# MainBoard_V2.net
KiCad netlist of a schematic drawn in Altium Designer
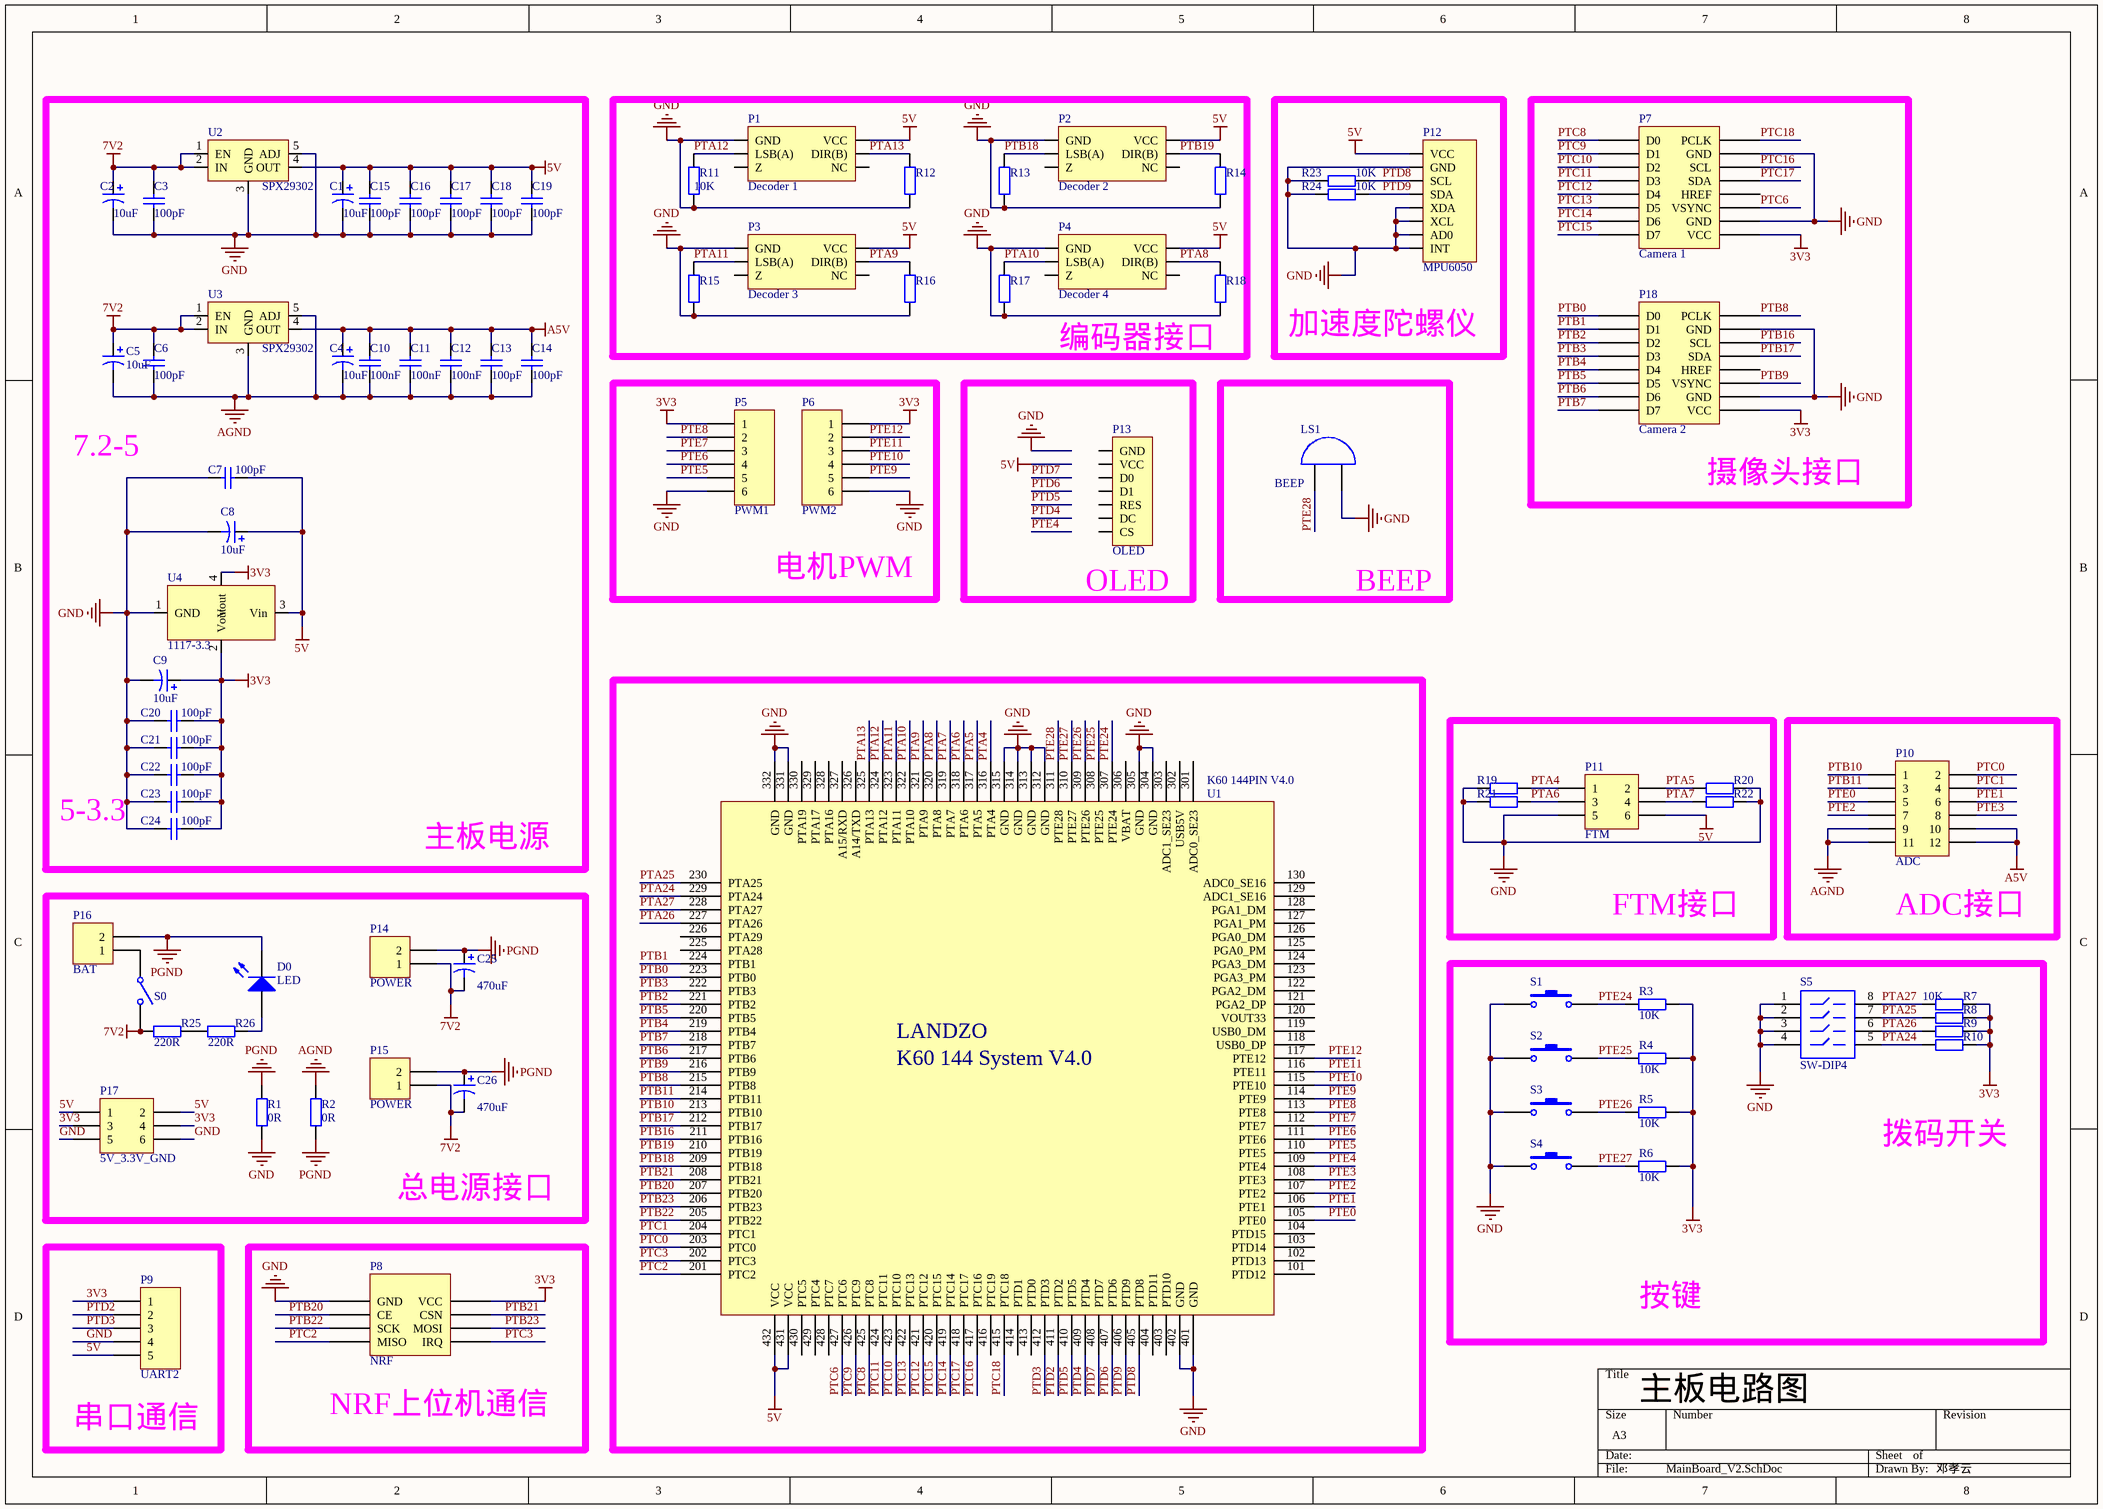
[diagram p0: MainBoard_V2.SchDoc]

(export (version "E")
  (design (tool "Eeschema 10.0.6"))
  (components
    (comp (ref "C1")
      (value "10uF")
      (footprint "1206 C tan")
      (description "Polarized Capacitor (Radial)")
      (fields (field (name "Comment") "Cap Pol1"))
      (libsource (lib "Miscellaneous Devices") (part "Cap Pol1"))
    )
    (comp (ref "C2")
      (value "10uF")
      (footprint "1206 C tan")
      (description "Polarized Capacitor (Radial)")
      (fields (field (name "Comment") "Cap Pol1"))
      (libsource (lib "Miscellaneous Devices") (part "Cap Pol1"))
    )
    (comp (ref "C3")
      (value "100pF")
      (footprint "1206 C")
      (description "Capacitor (Semiconductor SIM Model)")
      (fields (field (name "Comment") "Cap Semi"))
      (libsource (lib "Miscellaneous Devices") (part "Cap Semi"))
    )
    (comp (ref "C4")
      (value "10uF")
      (footprint "1206 C tan")
      (description "Polarized Capacitor (Radial)")
      (fields (field (name "Comment") "Cap Pol1"))
      (libsource (lib "Miscellaneous Devices") (part "Cap Pol1"))
    )
    (comp (ref "C5")
      (value "10uF")
      (footprint "1206 C tan")
      (description "Polarized Capacitor (Radial)")
      (fields (field (name "Comment") "Cap Pol1"))
      (libsource (lib "Miscellaneous Devices") (part "Cap Pol1"))
    )
    (comp (ref "C6")
      (value "100pF")
      (footprint "1206 C")
      (description "Capacitor (Semiconductor SIM Model)")
      (fields (field (name "Comment") "Cap Semi"))
      (libsource (lib "Miscellaneous Devices") (part "Cap Semi"))
    )
    (comp (ref "C7")
      (value "100pF")
      (footprint "1206 C")
      (description "Capacitor (Semiconductor SIM Model)")
      (fields (field (name "Comment") "Cap Semi"))
      (libsource (lib "Miscellaneous Devices") (part "Cap Semi"))
    )
    (comp (ref "C8")
      (value "10uF")
      (footprint "1206 C tan")
      (description "Polarized Capacitor (Radial)")
      (fields (field (name "Comment") "Cap Pol1"))
      (libsource (lib "Miscellaneous Devices") (part "Cap Pol1"))
    )
    (comp (ref "C9")
      (value "10uF")
      (footprint "1206 C tan")
      (description "Polarized Capacitor (Radial)")
      (fields (field (name "Comment") "Cap Pol1"))
      (libsource (lib "Miscellaneous Devices") (part "Cap Pol1"))
    )
    (comp (ref "C10")
      (value "100nF")
      (footprint "0805 C")
      (description "Capacitor")
      (fields (field (name "Comment") "Cap"))
      (libsource (lib "Miscellaneous Devices") (part "Cap"))
    )
    (comp (ref "C11")
      (value "100nF")
      (footprint "0805 C")
      (description "Capacitor")
      (fields (field (name "Comment") "Cap"))
      (libsource (lib "Miscellaneous Devices") (part "Cap"))
    )
    (comp (ref "C12")
      (value "100nF")
      (footprint "0805 C")
      (description "Capacitor")
      (fields (field (name "Comment") "Cap"))
      (libsource (lib "Miscellaneous Devices") (part "Cap"))
    )
    (comp (ref "C13")
      (value "100pF")
      (footprint "0805 C")
      (description "Capacitor")
      (fields (field (name "Comment") "Cap"))
      (libsource (lib "Miscellaneous Devices") (part "Cap"))
    )
    (comp (ref "C14")
      (value "100pF")
      (footprint "0805 C")
      (description "Capacitor")
      (fields (field (name "Comment") "Cap"))
      (libsource (lib "Miscellaneous Devices") (part "Cap"))
    )
    (comp (ref "C15")
      (value "100pF")
      (footprint "0805 C")
      (description "Capacitor")
      (fields (field (name "Comment") "Cap"))
      (libsource (lib "Miscellaneous Devices") (part "Cap"))
    )
    (comp (ref "C16")
      (value "100pF")
      (footprint "0805 C")
      (description "Capacitor")
      (fields (field (name "Comment") "Cap"))
      (libsource (lib "Miscellaneous Devices") (part "Cap"))
    )
    (comp (ref "C17")
      (value "100pF")
      (footprint "0805 C")
      (description "Capacitor")
      (fields (field (name "Comment") "Cap"))
      (libsource (lib "Miscellaneous Devices") (part "Cap"))
    )
    (comp (ref "C18")
      (value "100pF")
      (footprint "0805 C")
      (description "Capacitor")
      (fields (field (name "Comment") "Cap"))
      (libsource (lib "Miscellaneous Devices") (part "Cap"))
    )
    (comp (ref "C19")
      (value "100pF")
      (footprint "0805 C")
      (description "Capacitor")
      (fields (field (name "Comment") "Cap"))
      (libsource (lib "Miscellaneous Devices") (part "Cap"))
    )
    (comp (ref "C20")
      (value "100pF")
      (footprint "0805 C")
      (description "Capacitor")
      (fields (field (name "Comment") "Cap"))
      (libsource (lib "Miscellaneous Devices") (part "Cap"))
    )
    (comp (ref "C21")
      (value "100pF")
      (footprint "0805 C")
      (description "Capacitor")
      (fields (field (name "Comment") "Cap"))
      (libsource (lib "Miscellaneous Devices") (part "Cap"))
    )
    (comp (ref "C22")
      (value "100pF")
      (footprint "0805 C")
      (description "Capacitor")
      (fields (field (name "Comment") "Cap"))
      (libsource (lib "Miscellaneous Devices") (part "Cap"))
    )
    (comp (ref "C23")
      (value "100pF")
      (footprint "0805 C")
      (description "Capacitor")
      (fields (field (name "Comment") "Cap"))
      (libsource (lib "Miscellaneous Devices") (part "Cap"))
    )
    (comp (ref "C24")
      (value "100pF")
      (footprint "0805 C")
      (description "Capacitor")
      (fields (field (name "Comment") "Cap"))
      (libsource (lib "Miscellaneous Devices") (part "Cap"))
    )
    (comp (ref "C25")
      (value "470uF")
      (footprint "C pol")
      (description "Polarized Capacitor (Radial)")
      (fields (field (name "Comment") "Cap Pol1"))
      (libsource (lib "Miscellaneous Devices") (part "Cap Pol1"))
    )
    (comp (ref "C26")
      (value "470uF")
      (footprint "C pol")
      (description "Polarized Capacitor (Radial)")
      (fields (field (name "Comment") "Cap Pol1"))
      (libsource (lib "Miscellaneous Devices") (part "Cap Pol1"))
    )
    (comp (ref "D0")
      (value "LED")
      (footprint "0805 D")
      (description "Typical INFRARED GaAs LED")
      (libsource (lib "Miscellaneous Devices") (part "LED0"))
    )
    (comp (ref "K60 144PIN V4.0")
      (value "U1")
      (footprint "K60 V4.0")
      (description "Vcc5V。网标x代表排针。USB5V供外接USB使用的，不推荐使用。VBAT是给另一个晶振使用的，使用3.3V，可以不接。")
      (libsource (lib "最小系统板K60P144-V4.0") (part "K60 144PIN V4.0系统板"))
    )
    (comp (ref "LS1")
      (value "BEEP")
      (footprint "BEEP")
      (description "Electrical Bell")
      (libsource (lib "Miscellaneous Devices") (part "Bell"))
    )
    (comp (ref "P1")
      (value "Decoder 1")
      (footprint "BigHeader P3*2")
      (description "Header-6")
      (libsource (lib "Sch库") (part "Decoder"))
    )
    (comp (ref "P2")
      (value "Decoder 2")
      (footprint "BigHeader P3*2")
      (description "Header-6")
      (libsource (lib "Sch库") (part "Decoder"))
    )
    (comp (ref "P3")
      (value "Decoder 3")
      (footprint "BigHeader P3*2")
      (description "Header-6")
      (libsource (lib "Sch库") (part "Decoder"))
    )
    (comp (ref "P4")
      (value "Decoder 4")
      (footprint "BigHeader P3*2")
      (description "Header-6")
      (libsource (lib "Sch库") (part "Decoder"))
    )
    (comp (ref "P5")
      (value "PWM1")
      (footprint "Header P6")
      (description "Header, 6-Pin")
      (libsource (lib "") (part "Header 6_1"))
    )
    (comp (ref "P6")
      (value "PWM2")
      (footprint "Header P6")
      (description "Header, 6-Pin")
      (libsource (lib "Miscellaneous Connectors") (part "Header 6"))
    )
    (comp (ref "P7")
      (value "Camera 1")
      (footprint "FHeader P8*2")
      (description "3.3V")
      (libsource (lib "C车外接器件") (part "OV7725"))
    )
    (comp (ref "P8") (value "NRF") (footprint "NRF") (libsource (lib "C车外接器件") (part "NRF")))
    (comp (ref "P9")
      (value "UART2")
      (footprint "Header P5")
      (description "Header, 5-Pin")
      (libsource (lib "Miscellaneous Connectors") (part "Header 5"))
    )
    (comp (ref "P10")
      (value "ADC")
      (footprint "Header P6*2")
      (description "Header, 6-Pin, Dual row")
      (libsource (lib "Miscellaneous Connectors") (part "Header 6X2"))
    )
    (comp (ref "P11")
      (value "FTM")
      (footprint "Header P3*2")
      (description "Header, 3-Pin, Dual row")
      (libsource (lib "Miscellaneous Connectors") (part "Header 3X2"))
    )
    (comp (ref "P12")
      (value "MPU6050")
      (footprint "MPU6050")
      (description "Header-8")
      (libsource (lib "Sch库") (part "MPU6050"))
    )
    (comp (ref "P13")
      (value "OLED")
      (footprint "OLED P7")
      (description "Header-7")
      (libsource (lib "Sch库") (part "OLED"))
    )
    (comp (ref "P14")
      (value "POWER")
      (footprint "Connect 050-2")
      (description "Header, 2-Pin")
      (libsource (lib "Miscellaneous Connectors") (part "Header 2"))
    )
    (comp (ref "P15")
      (value "POWER")
      (footprint "Connect 050-2")
      (description "Header, 2-Pin")
      (libsource (lib "Miscellaneous Connectors") (part "Header 2"))
    )
    (comp (ref "P16")
      (value "BAT")
      (footprint "Connect 050-2")
      (description "Header, 2-Pin")
      (libsource (lib "Miscellaneous Connectors") (part "Header 2"))
    )
    (comp (ref "P17")
      (value "5V_3.3V_GND")
      (footprint "Header P3*2")
      (description "Header, 3-Pin, Dual row")
      (libsource (lib "Miscellaneous Connectors") (part "Header 3X2"))
    )
    (comp (ref "P18")
      (value "Camera 2")
      (footprint "FHeader P8*2")
      (description "3.3V")
      (libsource (lib "C车外接器件") (part "OV7725"))
    )
    (comp (ref "R1")
      (value "0R")
      (footprint "1206 R")
      (description "Resistor")
      (fields (field (name "Comment") "Res2"))
      (libsource (lib "Miscellaneous Devices") (part "Res2"))
    )
    (comp (ref "R2")
      (value "0R")
      (footprint "1206 R")
      (description "Resistor")
      (fields (field (name "Comment") "Res2"))
      (libsource (lib "Miscellaneous Devices") (part "Res2"))
    )
    (comp (ref "R3")
      (value "10K")
      (footprint "0805 R")
      (description "Resistor")
      (fields (field (name "Comment") "Res2"))
      (libsource (lib "") (part "Res2_1"))
    )
    (comp (ref "R4")
      (value "10K")
      (footprint "0805 R")
      (description "Resistor")
      (fields (field (name "Comment") "Res2"))
      (libsource (lib "") (part "Res2_1"))
    )
    (comp (ref "R5")
      (value "10K")
      (footprint "0805 R")
      (description "Resistor")
      (fields (field (name "Comment") "Res2"))
      (libsource (lib "") (part "Res2_1"))
    )
    (comp (ref "R6")
      (value "10K")
      (footprint "0805 R")
      (description "Resistor")
      (fields (field (name "Comment") "Res2"))
      (libsource (lib "") (part "Res2_1"))
    )
    (comp (ref "R7")
      (value "10K")
      (footprint "0805 R")
      (description "Resistor")
      (fields (field (name "Comment") "Res2"))
      (libsource (lib "") (part "Res2_1"))
    )
    (comp (ref "R8")
      (value "Res2")
      (footprint "0805 R")
      (description "Resistor")
      (libsource (lib "") (part "Res2_1"))
    )
    (comp (ref "R9")
      (value "Res2")
      (footprint "0805 R")
      (description "Resistor")
      (libsource (lib "") (part "Res2_1"))
    )
    (comp (ref "R10")
      (value "Res2")
      (footprint "0805 R")
      (description "Resistor")
      (libsource (lib "") (part "Res2_1"))
    )
    (comp (ref "R11")
      (value "10K")
      (footprint "0805 R")
      (description "Resistor")
      (fields (field (name "Comment") "Res2"))
      (libsource (lib "Miscellaneous Devices") (part "Res2"))
    )
    (comp (ref "R12")
      (value "Res2")
      (footprint "0805 R")
      (description "Resistor")
      (libsource (lib "Miscellaneous Devices") (part "Res2"))
    )
    (comp (ref "R13")
      (value "Res2")
      (footprint "0805 R")
      (description "Resistor")
      (libsource (lib "Miscellaneous Devices") (part "Res2"))
    )
    (comp (ref "R14")
      (value "Res2")
      (footprint "0805 R")
      (description "Resistor")
      (libsource (lib "Miscellaneous Devices") (part "Res2"))
    )
    (comp (ref "R15")
      (value "Res2")
      (footprint "0805 R")
      (description "Resistor")
      (libsource (lib "Miscellaneous Devices") (part "Res2"))
    )
    (comp (ref "R16")
      (value "Res2")
      (footprint "0805 R")
      (description "Resistor")
      (libsource (lib "Miscellaneous Devices") (part "Res2"))
    )
    (comp (ref "R17")
      (value "Res2")
      (footprint "0805 R")
      (description "Resistor")
      (libsource (lib "Miscellaneous Devices") (part "Res2"))
    )
    (comp (ref "R18")
      (value "Res2")
      (footprint "0805 R")
      (description "Resistor")
      (libsource (lib "Miscellaneous Devices") (part "Res2"))
    )
    (comp (ref "R19")
      (value "Res2")
      (footprint "0805 R")
      (description "Resistor")
      (libsource (lib "") (part "Res2_1"))
    )
    (comp (ref "R20")
      (value "Res2")
      (footprint "0805 R")
      (description "Resistor")
      (libsource (lib "") (part "Res2_1"))
    )
    (comp (ref "R21")
      (value "Res2")
      (footprint "0805 R")
      (description "Resistor")
      (libsource (lib "") (part "Res2_1"))
    )
    (comp (ref "R22")
      (value "Res2")
      (footprint "0805 R")
      (description "Resistor")
      (libsource (lib "") (part "Res2_1"))
    )
    (comp (ref "R23")
      (value "10K")
      (footprint "0805 R")
      (description "Resistor")
      (fields (field (name "Comment") "Res2"))
      (libsource (lib "") (part "Res2_1"))
    )
    (comp (ref "R24")
      (value "10K")
      (footprint "0805 R")
      (description "Resistor")
      (fields (field (name "Comment") "Res2"))
      (libsource (lib "") (part "Res2_1"))
    )
    (comp (ref "R25")
      (value "220R")
      (footprint "0805 R")
      (description "Resistor")
      (fields (field (name "Comment") "Res2"))
      (libsource (lib "") (part "Res2_1"))
    )
    (comp (ref "R26")
      (value "220R")
      (footprint "0805 R")
      (description "Resistor")
      (fields (field (name "Comment") "Res2"))
      (libsource (lib "") (part "Res2_1"))
    )
    (comp (ref "S0")
      (value "SW-SPST")
      (footprint "Switch")
      (description "Single-Pole, Single-Throw Switch")
      (libsource (lib "Miscellaneous Devices") (part "SW-SPST"))
    )
    (comp (ref "S1")
      (value "SW-PB")
      (footprint "Touch Switch")
      (description "Switch")
      (libsource (lib "Miscellaneous Devices") (part "SW-PB"))
    )
    (comp (ref "S2")
      (value "SW-PB")
      (footprint "Touch Switch")
      (description "Switch")
      (libsource (lib "Miscellaneous Devices") (part "SW-PB"))
    )
    (comp (ref "S3")
      (value "SW-PB")
      (footprint "Touch Switch")
      (description "Switch")
      (libsource (lib "Miscellaneous Devices") (part "SW-PB"))
    )
    (comp (ref "S4")
      (value "SW-PB")
      (footprint "Touch Switch")
      (description "Switch")
      (libsource (lib "Miscellaneous Devices") (part "SW-PB"))
    )
    (comp (ref "S5")
      (value "SW-DIP4")
      (footprint "DIP-8")
      (description "DIP Switch")
      (libsource (lib "Miscellaneous Devices") (part "SW-DIP4"))
    )
    (comp (ref "U2") (value "SPX29302") (footprint "To-263-5") (libsource (lib "Sch库") (part "SPX29302")))
    (comp (ref "U3") (value "SPX29302") (footprint "To-263-5") (libsource (lib "Sch库") (part "SPX29302")))
    (comp (ref "U4") (value "1117-3.3") (footprint "SOT223_M") (libsource (lib "Sch库") (part "1117")))
  )
  (nets
    (net (code "1") (name "/PTA4") (class "Default")
      (node (ref "K60 144PIN V4.0") (pin "316") (pinfunction "PTA4_316") (pintype "passive"))
      (node (ref "P11") (pin "1") (pinfunction "1_1") (pintype "passive"))
      (node (ref "R19") (pin "2") (pinfunction "2_2") (pintype "passive"))
    )
    (net (code "2") (name "/PTA5") (class "Default")
      (node (ref "K60 144PIN V4.0") (pin "317") (pinfunction "PTA5_317") (pintype "passive"))
      (node (ref "P11") (pin "2") (pinfunction "2_2") (pintype "passive"))
      (node (ref "R20") (pin "1") (pinfunction "1_1") (pintype "passive"))
    )
    (net (code "3") (name "/PTA6") (class "Default")
      (node (ref "K60 144PIN V4.0") (pin "318") (pinfunction "PTA6_318") (pintype "passive"))
      (node (ref "P11") (pin "3") (pinfunction "3_3") (pintype "passive"))
      (node (ref "R21") (pin "2") (pinfunction "2_2") (pintype "passive"))
    )
    (net (code "4") (name "/PTA7") (class "Default")
      (node (ref "K60 144PIN V4.0") (pin "319") (pinfunction "PTA7_319") (pintype "passive"))
      (node (ref "P11") (pin "4") (pinfunction "4_4") (pintype "passive"))
      (node (ref "R22") (pin "1") (pinfunction "1_1") (pintype "passive"))
    )
    (net (code "5") (name "/PTA8") (class "Default")
      (node (ref "K60 144PIN V4.0") (pin "320") (pinfunction "PTA8_320") (pintype "passive"))
      (node (ref "P4") (pin "4") (pinfunction "DIR(B)_4") (pintype "passive"))
      (node (ref "R18") (pin "2") (pinfunction "2_2") (pintype "passive"))
    )
    (net (code "6") (name "/PTA9") (class "Default")
      (node (ref "K60 144PIN V4.0") (pin "321") (pinfunction "PTA9_321") (pintype "passive"))
      (node (ref "P3") (pin "4") (pinfunction "DIR(B)_4") (pintype "passive"))
      (node (ref "R16") (pin "2") (pinfunction "2_2") (pintype "passive"))
    )
    (net (code "7") (name "/PTA10") (class "Default")
      (node (ref "K60 144PIN V4.0") (pin "322") (pinfunction "PTA10_322") (pintype "passive"))
      (node (ref "P4") (pin "3") (pinfunction "LSB(A)_3") (pintype "passive"))
      (node (ref "R17") (pin "2") (pinfunction "2_2") (pintype "passive"))
    )
    (net (code "8") (name "/PTA11") (class "Default")
      (node (ref "K60 144PIN V4.0") (pin "323") (pinfunction "PTA11_323") (pintype "passive"))
      (node (ref "P3") (pin "3") (pinfunction "LSB(A)_3") (pintype "passive"))
      (node (ref "R15") (pin "2") (pinfunction "2_2") (pintype "passive"))
    )
    (net (code "9") (name "/PTA12") (class "Default")
      (node (ref "K60 144PIN V4.0") (pin "324") (pinfunction "PTA12_324") (pintype "passive"))
      (node (ref "P1") (pin "3") (pinfunction "LSB(A)_3") (pintype "passive"))
      (node (ref "R11") (pin "2") (pinfunction "2_2") (pintype "passive"))
    )
    (net (code "10") (name "/PTA13") (class "Default")
      (node (ref "K60 144PIN V4.0") (pin "325") (pinfunction "PTA13_325") (pintype "passive"))
      (node (ref "P1") (pin "4") (pinfunction "DIR(B)_4") (pintype "passive"))
      (node (ref "R12") (pin "2") (pinfunction "2_2") (pintype "passive"))
    )
    (net (code "11") (name "/PTA24") (class "Default")
      (node (ref "K60 144PIN V4.0") (pin "229") (pinfunction "PTA24_229") (pintype "passive"))
      (node (ref "R10") (pin "1") (pinfunction "1_1") (pintype "passive"))
      (node (ref "S5") (pin "5") (pinfunction "5_5") (pintype "passive"))
    )
    (net (code "12") (name "/PTA25") (class "Default")
      (node (ref "K60 144PIN V4.0") (pin "230") (pinfunction "PTA25_230") (pintype "passive"))
      (node (ref "R8") (pin "1") (pinfunction "1_1") (pintype "passive"))
      (node (ref "S5") (pin "7") (pinfunction "7_7") (pintype "passive"))
    )
    (net (code "13") (name "/PTA26") (class "Default")
      (node (ref "K60 144PIN V4.0") (pin "227") (pinfunction "PTA26_227") (pintype "passive"))
      (node (ref "R9") (pin "1") (pinfunction "1_1") (pintype "passive"))
      (node (ref "S5") (pin "6") (pinfunction "6_6") (pintype "passive"))
    )
    (net (code "14") (name "/PTA27") (class "Default")
      (node (ref "K60 144PIN V4.0") (pin "228") (pinfunction "PTA27_228") (pintype "passive"))
      (node (ref "R7") (pin "1") (pinfunction "1_1") (pintype "passive"))
      (node (ref "S5") (pin "8") (pinfunction "8_8") (pintype "passive"))
    )
    (net (code "15") (name "/PTB0") (class "Default")
      (node (ref "K60 144PIN V4.0") (pin "223") (pinfunction "PTB0_223") (pintype "passive"))
      (node (ref "P18") (pin "1") (pinfunction "D0_1") (pintype "passive"))
    )
    (net (code "16") (name "/PTB1") (class "Default")
      (node (ref "K60 144PIN V4.0") (pin "224") (pinfunction "PTB1_224") (pintype "passive"))
      (node (ref "P18") (pin "2") (pinfunction "D1_2") (pintype "passive"))
    )
    (net (code "17") (name "/PTB2") (class "Default")
      (node (ref "K60 144PIN V4.0") (pin "221") (pinfunction "PTB2_221") (pintype "passive"))
      (node (ref "P18") (pin "3") (pinfunction "D2_3") (pintype "passive"))
    )
    (net (code "18") (name "/PTB3") (class "Default")
      (node (ref "K60 144PIN V4.0") (pin "222") (pinfunction "PTB3_222") (pintype "passive"))
      (node (ref "P18") (pin "4") (pinfunction "D3_4") (pintype "passive"))
    )
    (net (code "19") (name "/PTB4") (class "Default")
      (node (ref "K60 144PIN V4.0") (pin "219") (pinfunction "PTB4_219") (pintype "passive"))
      (node (ref "P18") (pin "5") (pinfunction "D4_5") (pintype "passive"))
    )
    (net (code "20") (name "/PTB5") (class "Default")
      (node (ref "K60 144PIN V4.0") (pin "220") (pinfunction "PTB5_220") (pintype "passive"))
      (node (ref "P18") (pin "6") (pinfunction "D5_6") (pintype "passive"))
    )
    (net (code "21") (name "/PTB6") (class "Default")
      (node (ref "K60 144PIN V4.0") (pin "217") (pinfunction "PTB6_217") (pintype "passive"))
      (node (ref "P18") (pin "7") (pinfunction "D6_7") (pintype "passive"))
    )
    (net (code "22") (name "/PTB7") (class "Default")
      (node (ref "K60 144PIN V4.0") (pin "218") (pinfunction "PTB7_218") (pintype "passive"))
      (node (ref "P18") (pin "8") (pinfunction "D7_8") (pintype "passive"))
    )
    (net (code "23") (name "/PTB8") (class "Default")
      (node (ref "K60 144PIN V4.0") (pin "215") (pinfunction "PTB8_215") (pintype "passive"))
      (node (ref "P18") (pin "16") (pinfunction "PCLK_16") (pintype "passive"))
    )
    (net (code "24") (name "/PTB9") (class "Default")
      (node (ref "K60 144PIN V4.0") (pin "216") (pinfunction "PTB9_216") (pintype "passive"))
      (node (ref "P18") (pin "11") (pinfunction "VSYNC_11") (pintype "passive"))
    )
    (net (code "25") (name "/PTB10") (class "Default")
      (node (ref "K60 144PIN V4.0") (pin "213") (pinfunction "PTB10_213") (pintype "passive"))
      (node (ref "P10") (pin "1") (pinfunction "1_1") (pintype "passive"))
    )
    (net (code "26") (name "/PTB11") (class "Default")
      (node (ref "K60 144PIN V4.0") (pin "214") (pinfunction "PTB11_214") (pintype "passive"))
      (node (ref "P10") (pin "3") (pinfunction "3_3") (pintype "passive"))
    )
    (net (code "27") (name "/PTB16") (class "Default")
      (node (ref "K60 144PIN V4.0") (pin "211") (pinfunction "PTB16_211") (pintype "passive"))
      (node (ref "P18") (pin "14") (pinfunction "SCL_14") (pintype "passive"))
    )
    (net (code "28") (name "/PTB17") (class "Default")
      (node (ref "K60 144PIN V4.0") (pin "212") (pinfunction "PTB17_212") (pintype "passive"))
      (node (ref "P18") (pin "13") (pinfunction "SDA_13") (pintype "passive"))
    )
    (net (code "29") (name "/PTB18") (class "Default")
      (node (ref "K60 144PIN V4.0") (pin "209") (pinfunction "PTB18_209") (pintype "passive"))
      (node (ref "P2") (pin "3") (pinfunction "LSB(A)_3") (pintype "passive"))
      (node (ref "R13") (pin "2") (pinfunction "2_2") (pintype "passive"))
    )
    (net (code "30") (name "/PTB19") (class "Default")
      (node (ref "K60 144PIN V4.0") (pin "210") (pinfunction "PTB19_210") (pintype "passive"))
      (node (ref "P2") (pin "4") (pinfunction "DIR(B)_4") (pintype "passive"))
      (node (ref "R14") (pin "2") (pinfunction "2_2") (pintype "passive"))
    )
    (net (code "31") (name "/PTB20") (class "Default")
      (node (ref "K60 144PIN V4.0") (pin "207") (pinfunction "PTB20_207") (pintype "passive"))
      (node (ref "P8") (pin "2") (pinfunction "CE_2") (pintype "passive"))
    )
    (net (code "32") (name "/PTB21") (class "Default")
      (node (ref "K60 144PIN V4.0") (pin "208") (pinfunction "PTB21_208") (pintype "passive"))
      (node (ref "P8") (pin "7") (pinfunction "CSN_7") (pintype "passive"))
    )
    (net (code "33") (name "/PTB22") (class "Default")
      (node (ref "K60 144PIN V4.0") (pin "205") (pinfunction "PTB22_205") (pintype "passive"))
      (node (ref "P8") (pin "3") (pinfunction "SCK_3") (pintype "passive"))
    )
    (net (code "34") (name "/PTB23") (class "Default")
      (node (ref "K60 144PIN V4.0") (pin "206") (pinfunction "PTB23_206") (pintype "passive"))
      (node (ref "P8") (pin "6") (pinfunction "MOSI_6") (pintype "passive"))
    )
    (net (code "35") (name "/PTC0") (class "Default")
      (node (ref "K60 144PIN V4.0") (pin "203") (pinfunction "PTC0_203") (pintype "passive"))
      (node (ref "P10") (pin "2") (pinfunction "2_2") (pintype "passive"))
    )
    (net (code "36") (name "/PTC1") (class "Default")
      (node (ref "K60 144PIN V4.0") (pin "204") (pinfunction "PTC1_204") (pintype "passive"))
      (node (ref "P10") (pin "4") (pinfunction "4_4") (pintype "passive"))
    )
    (net (code "37") (name "/PTC2") (class "Default")
      (node (ref "K60 144PIN V4.0") (pin "201") (pinfunction "PTC2_201") (pintype "passive"))
      (node (ref "P8") (pin "4") (pinfunction "MISO_4") (pintype "passive"))
    )
    (net (code "38") (name "/PTC3") (class "Default")
      (node (ref "K60 144PIN V4.0") (pin "202") (pinfunction "PTC3_202") (pintype "passive"))
      (node (ref "P8") (pin "5") (pinfunction "IRQ_5") (pintype "passive"))
    )
    (net (code "39") (name "/PTC6") (class "Default")
      (node (ref "K60 144PIN V4.0") (pin "427") (pinfunction "PTC6_427") (pintype "passive"))
      (node (ref "P7") (pin "11") (pinfunction "VSYNC_11") (pintype "passive"))
    )
    (net (code "40") (name "/PTC8") (class "Default")
      (node (ref "K60 144PIN V4.0") (pin "425") (pinfunction "PTC8_425") (pintype "passive"))
      (node (ref "P7") (pin "1") (pinfunction "D0_1") (pintype "passive"))
    )
    (net (code "41") (name "/PTC9") (class "Default")
      (node (ref "K60 144PIN V4.0") (pin "426") (pinfunction "PTC9_426") (pintype "passive"))
      (node (ref "P7") (pin "2") (pinfunction "D1_2") (pintype "passive"))
    )
    (net (code "42") (name "/PTC10") (class "Default")
      (node (ref "K60 144PIN V4.0") (pin "423") (pinfunction "PTC10_423") (pintype "passive"))
      (node (ref "P7") (pin "3") (pinfunction "D2_3") (pintype "passive"))
    )
    (net (code "43") (name "/PTC11") (class "Default")
      (node (ref "K60 144PIN V4.0") (pin "424") (pinfunction "PTC11_424") (pintype "passive"))
      (node (ref "P7") (pin "4") (pinfunction "D3_4") (pintype "passive"))
    )
    (net (code "44") (name "/PTC12") (class "Default")
      (node (ref "K60 144PIN V4.0") (pin "421") (pinfunction "PTC12_421") (pintype "passive"))
      (node (ref "P7") (pin "5") (pinfunction "D4_5") (pintype "passive"))
    )
    (net (code "45") (name "/PTC13") (class "Default")
      (node (ref "K60 144PIN V4.0") (pin "422") (pinfunction "PTC13_422") (pintype "passive"))
      (node (ref "P7") (pin "6") (pinfunction "D5_6") (pintype "passive"))
    )
    (net (code "46") (name "/PTC14") (class "Default")
      (node (ref "K60 144PIN V4.0") (pin "419") (pinfunction "PTC14_419") (pintype "passive"))
      (node (ref "P7") (pin "7") (pinfunction "D6_7") (pintype "passive"))
    )
    (net (code "47") (name "/PTC15") (class "Default")
      (node (ref "K60 144PIN V4.0") (pin "420") (pinfunction "PTC15_420") (pintype "passive"))
      (node (ref "P7") (pin "8") (pinfunction "D7_8") (pintype "passive"))
    )
    (net (code "48") (name "/PTC16") (class "Default")
      (node (ref "K60 144PIN V4.0") (pin "417") (pinfunction "PTC16_417") (pintype "passive"))
      (node (ref "P7") (pin "14") (pinfunction "SCL_14") (pintype "passive"))
    )
    (net (code "49") (name "/PTC17") (class "Default")
      (node (ref "K60 144PIN V4.0") (pin "418") (pinfunction "PTC17_418") (pintype "passive"))
      (node (ref "P7") (pin "13") (pinfunction "SDA_13") (pintype "passive"))
    )
    (net (code "50") (name "/PTC18") (class "Default")
      (node (ref "K60 144PIN V4.0") (pin "415") (pinfunction "PTC18_415") (pintype "passive"))
      (node (ref "P7") (pin "16") (pinfunction "PCLK_16") (pintype "passive"))
    )
    (net (code "51") (name "/PTD2") (class "Default")
      (node (ref "K60 144PIN V4.0") (pin "411") (pinfunction "PTD2_411") (pintype "passive"))
      (node (ref "P9") (pin "2") (pinfunction "2_2") (pintype "passive"))
    )
    (net (code "52") (name "/PTD3") (class "Default")
      (node (ref "K60 144PIN V4.0") (pin "412") (pinfunction "PTD3_412") (pintype "passive"))
      (node (ref "P9") (pin "3") (pinfunction "3_3") (pintype "passive"))
    )
    (net (code "53") (name "/PTD4") (class "Default")
      (node (ref "K60 144PIN V4.0") (pin "409") (pinfunction "PTD4_409") (pintype "passive"))
    )
    (net (code "54") (name "/PTD5") (class "Default")
      (node (ref "K60 144PIN V4.0") (pin "410") (pinfunction "PTD5_410") (pintype "passive"))
    )
    (net (code "55") (name "/PTD6") (class "Default")
      (node (ref "K60 144PIN V4.0") (pin "407") (pinfunction "PTD6_407") (pintype "passive"))
    )
    (net (code "56") (name "/PTD7") (class "Default")
      (node (ref "K60 144PIN V4.0") (pin "408") (pinfunction "PTD7_408") (pintype "passive"))
    )
    (net (code "57") (name "/PTD8") (class "Default")
      (node (ref "K60 144PIN V4.0") (pin "405") (pinfunction "PTD8_405") (pintype "passive"))
      (node (ref "P12") (pin "3") (pinfunction "SCL_3") (pintype "passive"))
      (node (ref "R23") (pin "2") (pinfunction "2_2") (pintype "passive"))
    )
    (net (code "58") (name "/PTD9") (class "Default")
      (node (ref "K60 144PIN V4.0") (pin "406") (pinfunction "PTD9_406") (pintype "passive"))
      (node (ref "P12") (pin "4") (pinfunction "SDA_4") (pintype "passive"))
      (node (ref "R24") (pin "2") (pinfunction "2_2") (pintype "passive"))
    )
    (net (code "59") (name "/PTE0") (class "Default")
      (node (ref "K60 144PIN V4.0") (pin "105") (pinfunction "PTE0_105") (pintype "passive"))
      (node (ref "P10") (pin "5") (pinfunction "5_5") (pintype "passive"))
    )
    (net (code "60") (name "/PTE1") (class "Default")
      (node (ref "K60 144PIN V4.0") (pin "106") (pinfunction "PTE1_106") (pintype "passive"))
      (node (ref "P10") (pin "6") (pinfunction "6_6") (pintype "passive"))
    )
    (net (code "61") (name "/PTE2") (class "Default")
      (node (ref "K60 144PIN V4.0") (pin "107") (pinfunction "PTE2_107") (pintype "passive"))
      (node (ref "P10") (pin "7") (pinfunction "7_7") (pintype "passive"))
    )
    (net (code "62") (name "/PTE3") (class "Default")
      (node (ref "K60 144PIN V4.0") (pin "108") (pinfunction "PTE3_108") (pintype "passive"))
      (node (ref "P10") (pin "8") (pinfunction "8_8") (pintype "passive"))
    )
    (net (code "63") (name "/PTE4") (class "Default")
      (node (ref "K60 144PIN V4.0") (pin "109") (pinfunction "PTE4_109") (pintype "passive"))
    )
    (net (code "64") (name "/PTE5") (class "Default")
      (node (ref "K60 144PIN V4.0") (pin "110") (pinfunction "PTE5_110") (pintype "passive"))
      (node (ref "P5") (pin "5") (pinfunction "5_5") (pintype "passive"))
    )
    (net (code "65") (name "/PTE6") (class "Default")
      (node (ref "K60 144PIN V4.0") (pin "111") (pinfunction "PTE6_111") (pintype "passive"))
      (node (ref "P5") (pin "4") (pinfunction "4_4") (pintype "passive"))
    )
    (net (code "66") (name "/PTE7") (class "Default")
      (node (ref "K60 144PIN V4.0") (pin "112") (pinfunction "PTE7_112") (pintype "passive"))
      (node (ref "P5") (pin "3") (pinfunction "3_3") (pintype "passive"))
    )
    (net (code "67") (name "/PTE8") (class "Default")
      (node (ref "K60 144PIN V4.0") (pin "113") (pinfunction "PTE8_113") (pintype "passive"))
      (node (ref "P5") (pin "2") (pinfunction "2_2") (pintype "passive"))
    )
    (net (code "68") (name "/PTE9") (class "Default")
      (node (ref "K60 144PIN V4.0") (pin "114") (pinfunction "PTE9_114") (pintype "passive"))
      (node (ref "P6") (pin "5") (pinfunction "5_5") (pintype "passive"))
    )
    (net (code "69") (name "/PTE10") (class "Default")
      (node (ref "K60 144PIN V4.0") (pin "115") (pinfunction "PTE10_115") (pintype "passive"))
      (node (ref "P6") (pin "4") (pinfunction "4_4") (pintype "passive"))
    )
    (net (code "70") (name "/PTE11") (class "Default")
      (node (ref "K60 144PIN V4.0") (pin "116") (pinfunction "PTE11_116") (pintype "passive"))
      (node (ref "P6") (pin "3") (pinfunction "3_3") (pintype "passive"))
    )
    (net (code "71") (name "/PTE12") (class "Default")
      (node (ref "K60 144PIN V4.0") (pin "117") (pinfunction "PTE12_117") (pintype "passive"))
      (node (ref "P6") (pin "2") (pinfunction "2_2") (pintype "passive"))
    )
    (net (code "72") (name "/PTE24") (class "Default")
      (node (ref "K60 144PIN V4.0") (pin "307") (pinfunction "PTE24_307") (pintype "passive"))
      (node (ref "R3") (pin "1") (pinfunction "1_1") (pintype "passive"))
      (node (ref "S1") (pin "2") (pinfunction "2_2") (pintype "passive"))
    )
    (net (code "73") (name "/PTE25") (class "Default")
      (node (ref "K60 144PIN V4.0") (pin "308") (pinfunction "PTE25_308") (pintype "passive"))
      (node (ref "R4") (pin "1") (pinfunction "1_1") (pintype "passive"))
      (node (ref "S2") (pin "2") (pinfunction "2_2") (pintype "passive"))
    )
    (net (code "74") (name "/PTE26") (class "Default")
      (node (ref "K60 144PIN V4.0") (pin "309") (pinfunction "PTE26_309") (pintype "passive"))
      (node (ref "R5") (pin "1") (pinfunction "1_1") (pintype "passive"))
      (node (ref "S3") (pin "2") (pinfunction "2_2") (pintype "passive"))
    )
    (net (code "75") (name "/PTE27") (class "Default")
      (node (ref "K60 144PIN V4.0") (pin "310") (pinfunction "PTE27_310") (pintype "passive"))
      (node (ref "R6") (pin "1") (pinfunction "1_1") (pintype "passive"))
      (node (ref "S4") (pin "2") (pinfunction "2_2") (pintype "passive"))
    )
    (net (code "76") (name "/PTE28") (class "Default")
      (node (ref "K60 144PIN V4.0") (pin "311") (pinfunction "PTE28_311") (pintype "passive"))
      (node (ref "LS1") (pin "1") (pinfunction "A_1") (pintype "passive"))
    )
    (net (code "77") (name "3V3") (class "Default")
      (node (ref "C20") (pin "2") (pinfunction "2_2") (pintype "passive"))
      (node (ref "C21") (pin "2") (pinfunction "2_2") (pintype "passive"))
      (node (ref "C22") (pin "2") (pinfunction "2_2") (pintype "passive"))
      (node (ref "C23") (pin "2") (pinfunction "2_2") (pintype "passive"))
      (node (ref "C24") (pin "2") (pinfunction "2_2") (pintype "passive"))
      (node (ref "C9") (pin "1") (pinfunction "1_1") (pintype "passive"))
      (node (ref "P17") (pin "3") (pinfunction "3_3") (pintype "passive"))
      (node (ref "P17") (pin "4") (pinfunction "4_4") (pintype "passive"))
      (node (ref "P18") (pin "9") (pinfunction "VCC_9") (pintype "passive"))
      (node (ref "P5") (pin "1") (pinfunction "1_1") (pintype "passive"))
      (node (ref "P6") (pin "1") (pinfunction "1_1") (pintype "passive"))
      (node (ref "P7") (pin "9") (pinfunction "VCC_9") (pintype "passive"))
      (node (ref "P8") (pin "8") (pinfunction "VCC_8") (pintype "passive"))
      (node (ref "P9") (pin "1") (pinfunction "1_1") (pintype "passive"))
      (node (ref "R10") (pin "2") (pinfunction "2_2") (pintype "passive"))
      (node (ref "R3") (pin "2") (pinfunction "2_2") (pintype "passive"))
      (node (ref "R4") (pin "2") (pinfunction "2_2") (pintype "passive"))
      (node (ref "R5") (pin "2") (pinfunction "2_2") (pintype "passive"))
      (node (ref "R6") (pin "2") (pinfunction "2_2") (pintype "passive"))
      (node (ref "R7") (pin "2") (pinfunction "2_2") (pintype "passive"))
      (node (ref "R8") (pin "2") (pinfunction "2_2") (pintype "passive"))
      (node (ref "R9") (pin "2") (pinfunction "2_2") (pintype "passive"))
      (node (ref "U4") (pin "2") (pinfunction "Vout_2") (pintype "passive"))
      (node (ref "U4") (pin "4") (pinfunction "Vout_4") (pintype "passive"))
    )
    (net (code "78") (name "5V") (class "Default")
      (node (ref "C1") (pin "1") (pinfunction "1_1") (pintype "passive"))
      (node (ref "C15") (pin "2") (pinfunction "2_2") (pintype "passive"))
      (node (ref "C16") (pin "2") (pinfunction "2_2") (pintype "passive"))
      (node (ref "C17") (pin "2") (pinfunction "2_2") (pintype "passive"))
      (node (ref "C18") (pin "2") (pinfunction "2_2") (pintype "passive"))
      (node (ref "C19") (pin "2") (pinfunction "2_2") (pintype "passive"))
      (node (ref "C7") (pin "2") (pinfunction "2_2") (pintype "passive"))
      (node (ref "C8") (pin "1") (pinfunction "1_1") (pintype "passive"))
      (node (ref "K60 144PIN V4.0") (pin "431") (pinfunction "VCC_431") (pintype "passive"))
      (node (ref "K60 144PIN V4.0") (pin "432") (pinfunction "VCC_432") (pintype "passive"))
      (node (ref "P1") (pin "2") (pinfunction "VCC_2") (pintype "passive"))
      (node (ref "P11") (pin "6") (pinfunction "6_6") (pintype "passive"))
      (node (ref "P12") (pin "1") (pinfunction "VCC_1") (pintype "passive"))
      (node (ref "P17") (pin "1") (pinfunction "1_1") (pintype "passive"))
      (node (ref "P17") (pin "2") (pinfunction "2_2") (pintype "passive"))
      (node (ref "P2") (pin "2") (pinfunction "VCC_2") (pintype "passive"))
      (node (ref "P3") (pin "2") (pinfunction "VCC_2") (pintype "passive"))
      (node (ref "P4") (pin "2") (pinfunction "VCC_2") (pintype "passive"))
      (node (ref "P9") (pin "5") (pinfunction "5_5") (pintype "passive"))
      (node (ref "U2") (pin "4") (pinfunction "OUT_4") (pintype "passive"))
      (node (ref "U4") (pin "3") (pinfunction "Vin_3") (pintype "passive"))
    )
    (net (code "79") (name "7V2") (class "Default")
      (node (ref "C2") (pin "1") (pinfunction "1_1") (pintype "passive"))
      (node (ref "C25") (pin "2") (pinfunction "2_2") (pintype "passive"))
      (node (ref "C26") (pin "2") (pinfunction "2_2") (pintype "passive"))
      (node (ref "C3") (pin "2") (pinfunction "2_2") (pintype "passive"))
      (node (ref "C5") (pin "1") (pinfunction "1_1") (pintype "passive"))
      (node (ref "C6") (pin "2") (pinfunction "2_2") (pintype "passive"))
      (node (ref "P14") (pin "1") (pinfunction "1_1") (pintype "passive"))
      (node (ref "P15") (pin "1") (pinfunction "1_1") (pintype "passive"))
      (node (ref "R25") (pin "1") (pinfunction "1_1") (pintype "passive"))
      (node (ref "S0") (pin "2") (pinfunction "NO_2") (pintype "passive"))
      (node (ref "U2") (pin "1") (pinfunction "EN_1") (pintype "passive"))
      (node (ref "U2") (pin "2") (pinfunction "IN_2") (pintype "passive"))
      (node (ref "U3") (pin "1") (pinfunction "EN_1") (pintype "passive"))
      (node (ref "U3") (pin "2") (pinfunction "IN_2") (pintype "passive"))
    )
    (net (code "80") (name "A5V") (class "Default")
      (node (ref "C10") (pin "2") (pinfunction "2_2") (pintype "passive"))
      (node (ref "C11") (pin "2") (pinfunction "2_2") (pintype "passive"))
      (node (ref "C12") (pin "2") (pinfunction "2_2") (pintype "passive"))
      (node (ref "C13") (pin "2") (pinfunction "2_2") (pintype "passive"))
      (node (ref "C14") (pin "2") (pinfunction "2_2") (pintype "passive"))
      (node (ref "C4") (pin "1") (pinfunction "1_1") (pintype "passive"))
      (node (ref "P10") (pin "10") (pinfunction "10_10") (pintype "passive"))
      (node (ref "P10") (pin "12") (pinfunction "12_12") (pintype "passive"))
      (node (ref "U3") (pin "4") (pinfunction "OUT_4") (pintype "passive"))
    )
    (net (code "81") (name "AGND") (class "Default")
      (node (ref "C10") (pin "1") (pinfunction "1_1") (pintype "passive"))
      (node (ref "C11") (pin "1") (pinfunction "1_1") (pintype "passive"))
      (node (ref "C12") (pin "1") (pinfunction "1_1") (pintype "passive"))
      (node (ref "C13") (pin "1") (pinfunction "1_1") (pintype "passive"))
      (node (ref "C14") (pin "1") (pinfunction "1_1") (pintype "passive"))
      (node (ref "C4") (pin "2") (pinfunction "2_2") (pintype "passive"))
      (node (ref "C5") (pin "2") (pinfunction "2_2") (pintype "passive"))
      (node (ref "C6") (pin "1") (pinfunction "1_1") (pintype "passive"))
      (node (ref "P10") (pin "11") (pinfunction "11_11") (pintype "passive"))
      (node (ref "P10") (pin "9") (pinfunction "9_9") (pintype "passive"))
      (node (ref "R2") (pin "2") (pinfunction "2_2") (pintype "passive"))
      (node (ref "U3") (pin "3") (pinfunction "GND_3") (pintype "passive"))
      (node (ref "U3") (pin "5") (pinfunction "ADJ_5") (pintype "passive"))
    )
    (net (code "82") (name "GND") (class "Default")
      (node (ref "C1") (pin "2") (pinfunction "2_2") (pintype "passive"))
      (node (ref "C15") (pin "1") (pinfunction "1_1") (pintype "passive"))
      (node (ref "C16") (pin "1") (pinfunction "1_1") (pintype "passive"))
      (node (ref "C17") (pin "1") (pinfunction "1_1") (pintype "passive"))
      (node (ref "C18") (pin "1") (pinfunction "1_1") (pintype "passive"))
      (node (ref "C19") (pin "1") (pinfunction "1_1") (pintype "passive"))
      (node (ref "C2") (pin "2") (pinfunction "2_2") (pintype "passive"))
      (node (ref "C20") (pin "1") (pinfunction "1_1") (pintype "passive"))
      (node (ref "C21") (pin "1") (pinfunction "1_1") (pintype "passive"))
      (node (ref "C22") (pin "1") (pinfunction "1_1") (pintype "passive"))
      (node (ref "C23") (pin "1") (pinfunction "1_1") (pintype "passive"))
      (node (ref "C24") (pin "1") (pinfunction "1_1") (pintype "passive"))
      (node (ref "C3") (pin "1") (pinfunction "1_1") (pintype "passive"))
      (node (ref "C7") (pin "1") (pinfunction "1_1") (pintype "passive"))
      (node (ref "C8") (pin "2") (pinfunction "2_2") (pintype "passive"))
      (node (ref "C9") (pin "2") (pinfunction "2_2") (pintype "passive"))
      (node (ref "K60 144PIN V4.0") (pin "304") (pinfunction "GND_304") (pintype "passive"))
      (node (ref "K60 144PIN V4.0") (pin "305") (pinfunction "GND_305") (pintype "passive"))
      (node (ref "K60 144PIN V4.0") (pin "312") (pinfunction "GND_312") (pintype "passive"))
      (node (ref "K60 144PIN V4.0") (pin "313") (pinfunction "GND_313") (pintype "passive"))
      (node (ref "K60 144PIN V4.0") (pin "314") (pinfunction "GND_314") (pintype "passive"))
      (node (ref "K60 144PIN V4.0") (pin "315") (pinfunction "GND_315") (pintype "passive"))
      (node (ref "K60 144PIN V4.0") (pin "331") (pinfunction "GND_331") (pintype "passive"))
      (node (ref "K60 144PIN V4.0") (pin "332") (pinfunction "GND_332") (pintype "passive"))
      (node (ref "K60 144PIN V4.0") (pin "401") (pinfunction "GND_401") (pintype "passive"))
      (node (ref "K60 144PIN V4.0") (pin "402") (pinfunction "GND_402") (pintype "passive"))
      (node (ref "LS1") (pin "2") (pinfunction "B_2") (pintype "passive"))
      (node (ref "P1") (pin "1") (pinfunction "GND_1") (pintype "passive"))
      (node (ref "P11") (pin "5") (pinfunction "5_5") (pintype "passive"))
      (node (ref "P12") (pin "2") (pinfunction "GND_2") (pintype "passive"))
      (node (ref "P12") (pin "5") (pinfunction "XDA_5") (pintype "passive"))
      (node (ref "P12") (pin "6") (pinfunction "XCL_6") (pintype "passive"))
      (node (ref "P12") (pin "7") (pinfunction "AD0_7") (pintype "passive"))
      (node (ref "P12") (pin "8") (pinfunction "INT_8") (pintype "passive"))
      (node (ref "P17") (pin "5") (pinfunction "5_5") (pintype "passive"))
      (node (ref "P17") (pin "6") (pinfunction "6_6") (pintype "passive"))
      (node (ref "P18") (pin "10") (pinfunction "GND_10") (pintype "passive"))
      (node (ref "P18") (pin "15") (pinfunction "GND_15") (pintype "passive"))
      (node (ref "P2") (pin "1") (pinfunction "GND_1") (pintype "passive"))
      (node (ref "P3") (pin "1") (pinfunction "GND_1") (pintype "passive"))
      (node (ref "P4") (pin "1") (pinfunction "GND_1") (pintype "passive"))
      (node (ref "P5") (pin "6") (pinfunction "6_6") (pintype "passive"))
      (node (ref "P6") (pin "6") (pinfunction "6_6") (pintype "passive"))
      (node (ref "P7") (pin "10") (pinfunction "GND_10") (pintype "passive"))
      (node (ref "P7") (pin "15") (pinfunction "GND_15") (pintype "passive"))
      (node (ref "P8") (pin "1") (pinfunction "GND_1") (pintype "passive"))
      (node (ref "P9") (pin "4") (pinfunction "4_4") (pintype "passive"))
      (node (ref "R1") (pin "1") (pinfunction "1_1") (pintype "passive"))
      (node (ref "R11") (pin "1") (pinfunction "1_1") (pintype "passive"))
      (node (ref "R12") (pin "1") (pinfunction "1_1") (pintype "passive"))
      (node (ref "R13") (pin "1") (pinfunction "1_1") (pintype "passive"))
      (node (ref "R14") (pin "1") (pinfunction "1_1") (pintype "passive"))
      (node (ref "R15") (pin "1") (pinfunction "1_1") (pintype "passive"))
      (node (ref "R16") (pin "1") (pinfunction "1_1") (pintype "passive"))
      (node (ref "R17") (pin "1") (pinfunction "1_1") (pintype "passive"))
      (node (ref "R18") (pin "1") (pinfunction "1_1") (pintype "passive"))
      (node (ref "R19") (pin "1") (pinfunction "1_1") (pintype "passive"))
      (node (ref "R20") (pin "2") (pinfunction "2_2") (pintype "passive"))
      (node (ref "R21") (pin "1") (pinfunction "1_1") (pintype "passive"))
      (node (ref "R22") (pin "2") (pinfunction "2_2") (pintype "passive"))
      (node (ref "R23") (pin "1") (pinfunction "1_1") (pintype "passive"))
      (node (ref "R24") (pin "1") (pinfunction "1_1") (pintype "passive"))
      (node (ref "S1") (pin "1") (pinfunction "1_1") (pintype "passive"))
      (node (ref "S2") (pin "1") (pinfunction "1_1") (pintype "passive"))
      (node (ref "S3") (pin "1") (pinfunction "1_1") (pintype "passive"))
      (node (ref "S4") (pin "1") (pinfunction "1_1") (pintype "passive"))
      (node (ref "S5") (pin "1") (pinfunction "1_1") (pintype "passive"))
      (node (ref "S5") (pin "2") (pinfunction "2_2") (pintype "passive"))
      (node (ref "S5") (pin "3") (pinfunction "3_3") (pintype "passive"))
      (node (ref "S5") (pin "4") (pinfunction "4_4") (pintype "passive"))
      (node (ref "U2") (pin "3") (pinfunction "GND_3") (pintype "passive"))
      (node (ref "U2") (pin "5") (pinfunction "ADJ_5") (pintype "passive"))
      (node (ref "U4") (pin "1") (pinfunction "GND_1") (pintype "passive"))
    )
    (net (code "83") (name "Net-(D0-A)") (class "Default")
      (node (ref "D0") (pin "1") (pinfunction "A_1") (pintype "passive"))
      (node (ref "R26") (pin "2") (pinfunction "2_2") (pintype "passive"))
    )
    (net (code "84") (name "Net-(R25-Pad2)") (class "Default")
      (node (ref "R25") (pin "2") (pinfunction "2_2") (pintype "passive"))
      (node (ref "R26") (pin "1") (pinfunction "1_1") (pintype "passive"))
    )
    (net (code "85") (name "Net-(S0-COMMON)") (class "Default")
      (node (ref "P16") (pin "1") (pinfunction "1_1") (pintype "passive"))
      (node (ref "S0") (pin "1") (pinfunction "COMMON_1") (pintype "passive"))
    )
    (net (code "86") (name "PGND") (class "Default")
      (node (ref "C25") (pin "1") (pinfunction "1_1") (pintype "passive"))
      (node (ref "C26") (pin "1") (pinfunction "1_1") (pintype "passive"))
      (node (ref "D0") (pin "2") (pinfunction "K_2") (pintype "passive"))
      (node (ref "P14") (pin "2") (pinfunction "2_2") (pintype "passive"))
      (node (ref "P15") (pin "2") (pinfunction "2_2") (pintype "passive"))
      (node (ref "P16") (pin "2") (pinfunction "2_2") (pintype "passive"))
      (node (ref "R1") (pin "2") (pinfunction "2_2") (pintype "passive"))
      (node (ref "R2") (pin "1") (pinfunction "1_1") (pintype "passive"))
    )
    (net (code "87") (name "unconnected-(K60 144PIN V4.0-A14{slash}TXD-Pad326)") (class "Default")
      (node (ref "K60 144PIN V4.0") (pin "326") (pinfunction "A14/TXD_326") (pintype "passive"))
    )
    (net (code "88") (name "unconnected-(K60 144PIN V4.0-A15{slash}RXD-Pad327)") (class "Default")
      (node (ref "K60 144PIN V4.0") (pin "327") (pinfunction "A15/RXD_327") (pintype "passive"))
    )
    (net (code "89") (name "unconnected-(K60 144PIN V4.0-ADC0_SE16-Pad130)") (class "Default")
      (node (ref "K60 144PIN V4.0") (pin "130") (pinfunction "ADC0_SE16_130") (pintype "passive"))
    )
    (net (code "90") (name "unconnected-(K60 144PIN V4.0-ADC0_SE23-Pad301)") (class "Default")
      (node (ref "K60 144PIN V4.0") (pin "301") (pinfunction "ADC0_SE23_301") (pintype "passive"))
    )
    (net (code "91") (name "unconnected-(K60 144PIN V4.0-ADC1_SE16-Pad129)") (class "Default")
      (node (ref "K60 144PIN V4.0") (pin "129") (pinfunction "ADC1_SE16_129") (pintype "passive"))
    )
    (net (code "92") (name "unconnected-(K60 144PIN V4.0-ADC1_SE23-Pad303)") (class "Default")
      (node (ref "K60 144PIN V4.0") (pin "303") (pinfunction "ADC1_SE23_303") (pintype "passive"))
    )
    (net (code "93") (name "unconnected-(K60 144PIN V4.0-PGA0_DM-Pad126)") (class "Default")
      (node (ref "K60 144PIN V4.0") (pin "126") (pinfunction "PGA0_DM_126") (pintype "passive"))
    )
    (net (code "94") (name "unconnected-(K60 144PIN V4.0-PGA0_PM-Pad125)") (class "Default")
      (node (ref "K60 144PIN V4.0") (pin "125") (pinfunction "PGA0_PM_125") (pintype "passive"))
    )
    (net (code "95") (name "unconnected-(K60 144PIN V4.0-PGA1_DM-Pad128)") (class "Default")
      (node (ref "K60 144PIN V4.0") (pin "128") (pinfunction "PGA1_DM_128") (pintype "passive"))
    )
    (net (code "96") (name "unconnected-(K60 144PIN V4.0-PGA1_PM-Pad127)") (class "Default")
      (node (ref "K60 144PIN V4.0") (pin "127") (pinfunction "PGA1_PM_127") (pintype "passive"))
    )
    (net (code "97") (name "unconnected-(K60 144PIN V4.0-PGA2_DM-Pad122)") (class "Default")
      (node (ref "K60 144PIN V4.0") (pin "122") (pinfunction "PGA2_DM_122") (pintype "passive"))
    )
    (net (code "98") (name "unconnected-(K60 144PIN V4.0-PGA2_DP-Pad121)") (class "Default")
      (node (ref "K60 144PIN V4.0") (pin "121") (pinfunction "PGA2_DP_121") (pintype "passive"))
    )
    (net (code "99") (name "unconnected-(K60 144PIN V4.0-PGA3_DM-Pad124)") (class "Default")
      (node (ref "K60 144PIN V4.0") (pin "124") (pinfunction "PGA3_DM_124") (pintype "passive"))
    )
    (net (code "100") (name "unconnected-(K60 144PIN V4.0-PGA3_PM-Pad123)") (class "Default")
      (node (ref "K60 144PIN V4.0") (pin "123") (pinfunction "PGA3_PM_123") (pintype "passive"))
    )
    (net (code "101") (name "unconnected-(K60 144PIN V4.0-PTA16-Pad328)") (class "Default")
      (node (ref "K60 144PIN V4.0") (pin "328") (pinfunction "PTA16_328") (pintype "passive"))
    )
    (net (code "102") (name "unconnected-(K60 144PIN V4.0-PTA17-Pad329)") (class "Default")
      (node (ref "K60 144PIN V4.0") (pin "329") (pinfunction "PTA17_329") (pintype "passive"))
    )
    (net (code "103") (name "unconnected-(K60 144PIN V4.0-PTA19-Pad330)") (class "Default")
      (node (ref "K60 144PIN V4.0") (pin "330") (pinfunction "PTA19_330") (pintype "passive"))
    )
    (net (code "104") (name "unconnected-(K60 144PIN V4.0-PTA28-Pad225)") (class "Default")
      (node (ref "K60 144PIN V4.0") (pin "225") (pinfunction "PTA28_225") (pintype "passive"))
    )
    (net (code "105") (name "unconnected-(K60 144PIN V4.0-PTA29-Pad226)") (class "Default")
      (node (ref "K60 144PIN V4.0") (pin "226") (pinfunction "PTA29_226") (pintype "passive"))
    )
    (net (code "106") (name "unconnected-(K60 144PIN V4.0-PTC4-Pad429)") (class "Default")
      (node (ref "K60 144PIN V4.0") (pin "429") (pinfunction "PTC4_429") (pintype "passive"))
    )
    (net (code "107") (name "unconnected-(K60 144PIN V4.0-PTC5-Pad430)") (class "Default")
      (node (ref "K60 144PIN V4.0") (pin "430") (pinfunction "PTC5_430") (pintype "passive"))
    )
    (net (code "108") (name "unconnected-(K60 144PIN V4.0-PTC7-Pad428)") (class "Default")
      (node (ref "K60 144PIN V4.0") (pin "428") (pinfunction "PTC7_428") (pintype "passive"))
    )
    (net (code "109") (name "unconnected-(K60 144PIN V4.0-PTC19-Pad416)") (class "Default")
      (node (ref "K60 144PIN V4.0") (pin "416") (pinfunction "PTC19_416") (pintype "passive"))
    )
    (net (code "110") (name "unconnected-(K60 144PIN V4.0-PTD0-Pad413)") (class "Default")
      (node (ref "K60 144PIN V4.0") (pin "413") (pinfunction "PTD0_413") (pintype "passive"))
    )
    (net (code "111") (name "unconnected-(K60 144PIN V4.0-PTD1-Pad414)") (class "Default")
      (node (ref "K60 144PIN V4.0") (pin "414") (pinfunction "PTD1_414") (pintype "passive"))
    )
    (net (code "112") (name "unconnected-(K60 144PIN V4.0-PTD10-Pad403)") (class "Default")
      (node (ref "K60 144PIN V4.0") (pin "403") (pinfunction "PTD10_403") (pintype "passive"))
    )
    (net (code "113") (name "unconnected-(K60 144PIN V4.0-PTD11-Pad404)") (class "Default")
      (node (ref "K60 144PIN V4.0") (pin "404") (pinfunction "PTD11_404") (pintype "passive"))
    )
    (net (code "114") (name "unconnected-(K60 144PIN V4.0-PTD12-Pad101)") (class "Default")
      (node (ref "K60 144PIN V4.0") (pin "101") (pinfunction "PTD12_101") (pintype "passive"))
    )
    (net (code "115") (name "unconnected-(K60 144PIN V4.0-PTD13-Pad102)") (class "Default")
      (node (ref "K60 144PIN V4.0") (pin "102") (pinfunction "PTD13_102") (pintype "passive"))
    )
    (net (code "116") (name "unconnected-(K60 144PIN V4.0-PTD14-Pad103)") (class "Default")
      (node (ref "K60 144PIN V4.0") (pin "103") (pinfunction "PTD14_103") (pintype "passive"))
    )
    (net (code "117") (name "unconnected-(K60 144PIN V4.0-PTD15-Pad104)") (class "Default")
      (node (ref "K60 144PIN V4.0") (pin "104") (pinfunction "PTD15_104") (pintype "passive"))
    )
    (net (code "118") (name "unconnected-(K60 144PIN V4.0-USB0_DM-Pad119)") (class "Default")
      (node (ref "K60 144PIN V4.0") (pin "119") (pinfunction "USB0_DM_119") (pintype "passive"))
    )
    (net (code "119") (name "unconnected-(K60 144PIN V4.0-USB0_DP-Pad118)") (class "Default")
      (node (ref "K60 144PIN V4.0") (pin "118") (pinfunction "USB0_DP_118") (pintype "passive"))
    )
    (net (code "120") (name "unconnected-(K60 144PIN V4.0-USB5V-Pad302)") (class "Default")
      (node (ref "K60 144PIN V4.0") (pin "302") (pinfunction "USB5V_302") (pintype "passive"))
    )
    (net (code "121") (name "unconnected-(K60 144PIN V4.0-VBAT-Pad306)") (class "Default")
      (node (ref "K60 144PIN V4.0") (pin "306") (pinfunction "VBAT_306") (pintype "passive"))
    )
    (net (code "122") (name "unconnected-(K60 144PIN V4.0-VOUT33-Pad120)") (class "Default")
      (node (ref "K60 144PIN V4.0") (pin "120") (pinfunction "VOUT33_120") (pintype "passive"))
    )
    (net (code "123") (name "unconnected-(P1-NC-Pad6)") (class "Default")
      (node (ref "P1") (pin "6") (pinfunction "NC_6") (pintype "passive"))
    )
    (net (code "124") (name "unconnected-(P1-Z-Pad5)") (class "Default")
      (node (ref "P1") (pin "5") (pinfunction "Z_5") (pintype "passive"))
    )
    (net (code "125") (name "unconnected-(P2-NC-Pad6)") (class "Default")
      (node (ref "P2") (pin "6") (pinfunction "NC_6") (pintype "passive"))
    )
    (net (code "126") (name "unconnected-(P2-Z-Pad5)") (class "Default")
      (node (ref "P2") (pin "5") (pinfunction "Z_5") (pintype "passive"))
    )
    (net (code "127") (name "unconnected-(P3-NC-Pad6)") (class "Default")
      (node (ref "P3") (pin "6") (pinfunction "NC_6") (pintype "passive"))
    )
    (net (code "128") (name "unconnected-(P3-Z-Pad5)") (class "Default")
      (node (ref "P3") (pin "5") (pinfunction "Z_5") (pintype "passive"))
    )
    (net (code "129") (name "unconnected-(P4-NC-Pad6)") (class "Default")
      (node (ref "P4") (pin "6") (pinfunction "NC_6") (pintype "passive"))
    )
    (net (code "130") (name "unconnected-(P4-Z-Pad5)") (class "Default")
      (node (ref "P4") (pin "5") (pinfunction "Z_5") (pintype "passive"))
    )
    (net (code "131") (name "unconnected-(P7-HREF-Pad12)") (class "Default")
      (node (ref "P7") (pin "12") (pinfunction "HREF_12") (pintype "passive"))
    )
    (net (code "132") (name "unconnected-(P13-CS-Pad7)") (class "Default")
      (node (ref "P13") (pin "7") (pinfunction "CS_7") (pintype "passive"))
    )
    (net (code "133") (name "unconnected-(P13-D0-Pad3)") (class "Default")
      (node (ref "P13") (pin "3") (pinfunction "D0_3") (pintype "passive"))
    )
    (net (code "134") (name "unconnected-(P13-D1-Pad4)") (class "Default")
      (node (ref "P13") (pin "4") (pinfunction "D1_4") (pintype "passive"))
    )
    (net (code "135") (name "unconnected-(P13-DC-Pad6)") (class "Default")
      (node (ref "P13") (pin "6") (pinfunction "DC_6") (pintype "passive"))
    )
    (net (code "136") (name "unconnected-(P13-GND-Pad1)") (class "Default")
      (node (ref "P13") (pin "1") (pinfunction "GND_1") (pintype "passive"))
    )
    (net (code "137") (name "unconnected-(P13-RES-Pad5)") (class "Default")
      (node (ref "P13") (pin "5") (pinfunction "RES_5") (pintype "passive"))
    )
    (net (code "138") (name "unconnected-(P13-VCC-Pad2)") (class "Default")
      (node (ref "P13") (pin "2") (pinfunction "VCC_2") (pintype "passive"))
    )
    (net (code "139") (name "unconnected-(P18-HREF-Pad12)") (class "Default")
      (node (ref "P18") (pin "12") (pinfunction "HREF_12") (pintype "passive"))
    )
  )
)
